# PMIC_V2.net
KiCad netlist of a schematic drawn in Altium Designer
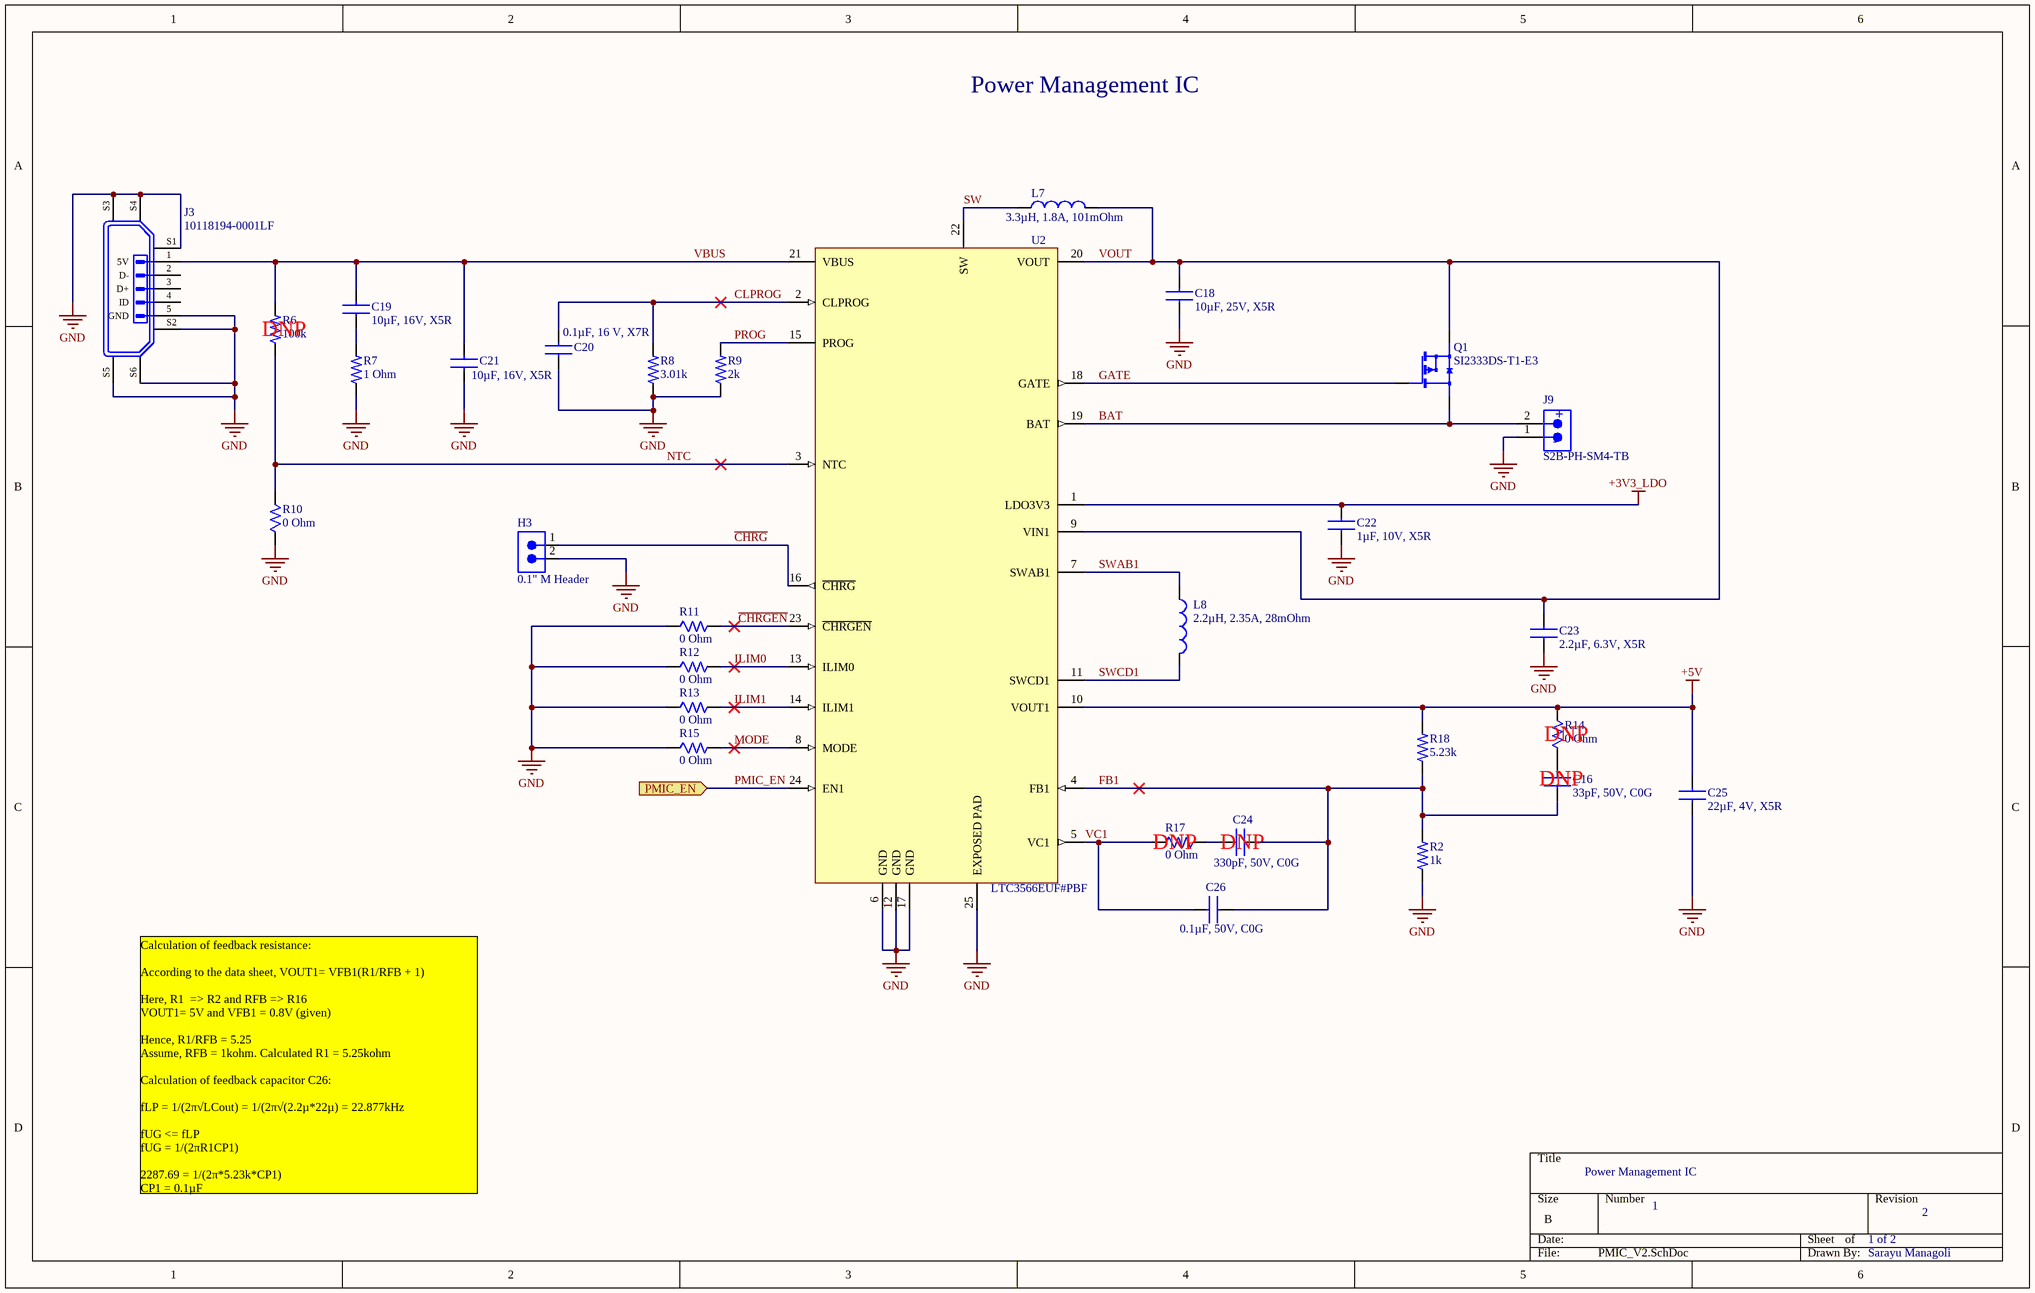
[diagram p0: PMIC_V2.SchDoc]

(export (version "E")
  (design (tool "Eeschema 10.0.6"))
  (components
    (comp (ref "C16")
      (value "33pF, 50V, C0G")
      (footprint "CAPC2012X09N_39P")
      (description "Cap Ceramic 33pF 50V C0G 5% SMD 0805 125C Paper T/R")
      (fields
        (field (name "MANUFACTURER") "KEMET")
        (field (name "MANUFACTURER PART NUMBER") "C0805C330J5GACTU")
      )
      (libsource (lib "PMIC_IR") (part "C0805C330J5GACTU"))
    )
    (comp (ref "C18")
      (value "10µF, 25V, X5R")
      (footprint "CAP_2012X14")
      (description "CAP CER 10UF 25V X5R 0805")
      (fields
        (field (name "MANUFACTURER") "Murata")
        (field (name "MANUFACTURER PART NUMBER") "GRM21BR61E106KA73K")
      )
      (libsource (lib "PMIC_IR") (part "GRM21BR61E106KA73K"))
    )
    (comp (ref "C19")
      (value "10µF, 16V, X5R")
      (footprint "CAP_2012X14")
      (description "CAP CER 10UF 16V X5R 0805")
      (fields
        (field (name "MANUFACTURER") "Murata")
        (field (name "MANUFACTURER PART NUMBER") "GRM21BR61C106KE15L")
      )
      (libsource (lib "PMIC_IR") (part "GRM21BR61C106KE15L"))
    )
    (comp (ref "C20")
      (value "0.1µF, 16 V, X7R")
      (footprint "CAPC2012X14N")
      (fields
        (field (name "MANUFACTURER") "Yageo")
        (field (name "MANUFACTURER PART NUMBER") "CC0805KRX7R7BB104")
        (field (name "TOLERANCE") "10%")
      )
      (libsource (lib "PMIC_IR") (part "CC0805KRX7R7BB104"))
    )
    (comp (ref "C21")
      (value "10µF, 16V, X5R")
      (footprint "CAP_2012X14")
      (description "CAP CER 10UF 16V X5R 0805")
      (fields
        (field (name "MANUFACTURER") "Murata")
        (field (name "MANUFACTURER PART NUMBER") "GRM21BR61C106KE15L")
      )
      (libsource (lib "PMIC_IR") (part "GRM21BR61C106KE15L"))
    )
    (comp (ref "C22")
      (value "1µF, 10V, X5R")
      (footprint "CAPC2012X14N_1")
      (description "CAP CER 1UF 10V X5R 0805")
      (fields
        (field (name "MANUFACTURER") "Kyocera AVX")
        (field (name "MANUFACTURER PART NUMBER") "0805ZD105KAT2A")
      )
      (libsource (lib "PMIC_IR") (part "0805ZD105KAT2A"))
    )
    (comp (ref "C23")
      (value "2.2µF, 6.3V, X5R")
      (footprint "CAPC2012X14N_2_2")
      (description "CAP CER 2.2UF 6.3V X5R 0805")
      (fields
        (field (name "MANUFACTURER") "Wurth Electronics")
        (field (name "MANUFACTURER PART NUMBER") "885012107001")
      )
      (libsource (lib "PMIC_IR") (part "885012107001"))
    )
    (comp (ref "C24")
      (value "330pF, 50V, C0G")
      (footprint "CAPC2012X09N_39P")
      (description "CAP CER 330PF 50V C0G/NP0 0805")
      (fields
        (field (name "MANUFACTURER") "KEMET")
        (field (name "MANUFACTURER PART NUMBER") "C0603C331K5GACTU")
      )
      (libsource (lib "PMIC_IR") (part "C0805C331K5GACTU"))
    )
    (comp (ref "C25")
      (value "22µF, 4V, X5R")
      (footprint "CAPC2012X14N_22")
      (description "CAP CER 22UF 4V X5R 0805")
      (fields
        (field (name "MANUFACTURER") "KEMET")
        (field (name "MANUFACTURER PART NUMBER") "C0805C226K7PAC7800")
      )
      (libsource (lib "PMIC_IR") (part "C0805C226K7PAC7800"))
    )
    (comp (ref "C26")
      (value "0.1µF, 50V, C0G")
      (footprint "CAPC2012X09N_39P")
      (description "0805 C 0.1µF Ceramic Multilayer Capacitor; 25 VDC; +125degC; C0G Dielec; +/-5%")
      (fields
        (field (name "MANUFACTURER") "KEMET")
        (field (name "MANUFACTURER PART NUMBER") "C0805C390J5GACTU")
      )
      (libsource (lib "PMIC_IR") (part "C0805C103J3GACTU"))
    )
    (comp (ref "H3")
      (value "0.1\" M Header")
      (footprint "77311-118-02LF_AMP")
      (description "Test point")
      (fields
        (field (name "MANUFACTURER") "Amphenol ICC / FCI")
        (field (name "MANUFACTURER PART NUMBER") "77311-118-02LF")
      )
      (libsource (lib "PMIC_IR") (part "77311-118-02LF"))
    )
    (comp (ref "J3")
      (value "micro-USB")
      (footprint "micro-USB")
      (description "10118194-0001LF micro-USB paste-in-pad")
      (fields
        (field (name "MANUFACTURER") "FCI")
        (field (name "MANUFACTURER PART NUMBER") "10118194-0001LF")
        (field (name ".CREATOR") "Kailey Shara")
        (field (name ".SCHCHECKED") "KS")
        (field (name ".PCBCHECKED") "KS")
      )
      (libsource (lib "PMIC_IR") (part "micro-USB"))
    )
    (comp (ref "J9")
      (value "S2B-PH-SM4-TB")
      (footprint "S2B-PH-SM4-TB")
      (description "JST PH Series, 2 Position, Side Entry, 2.00mm, Solder, Surface Mount, Natural")
      (fields
        (field (name "MANUFACTURER") "JST")
        (field (name "MANUFACTURER PART NUMBER") "S2B-PH-SM4-TB(LF)(SN)")
      )
      (libsource (lib "PMIC_IR") (part "S2B-PH-SM4-TB(LF)(SN)"))
    )
    (comp (ref "L7")
      (value "3.3µH, 1.8A, 101mOhm")
      (footprint "IND_2828x30")
      (fields
        (field (name "MANUFACTURER") "Wurth Electronics")
        (field (name "MANUFACTURER PART NUMBER") "744025003")
        (field (name "TOLERANCE") "20%")
      )
      (libsource (lib "PMIC_IR") (part "744025003"))
    )
    (comp (ref "L8")
      (value "2.2µH, 2.35A, 28mOhm")
      (footprint "INDP4848X30N_2_2")
      (fields
        (field (name "MANUFACTURER") "Wurth Electronics")
        (field (name "MANUFACTURER PART NUMBER") "7440430022")
        (field (name "TOLERANCE") "30%")
      )
      (libsource (lib "PMIC_IR") (part "7440430022"))
    )
    (comp (ref "Q1")
      (value "SI2333DS-T1-E3")
      (footprint "SOT95P237X112-3N")
      (description "Mosfet; Power; P-ch; Vdss -12V; Rds(on) 0.025 Ohm; Id -4.1A; TO-236 (SOT-23); Pd 0.75W")
      (fields (field (name "MANUFACTURER") "Vishay Siliconix"))
      (libsource (lib "PMIC_IR") (part "SI2333DS-T1-E3"))
    )
    (comp (ref "R2")
      (value "1k")
      (footprint "RESC1609X05N")
      (description "Res Thick Film 0603 1K Ohm 1% 1/10W ±100ppm/°C Molded SMD SMD T/R")
      (fields
        (field (name "MANUFACTURER") "Vishay")
        (field (name "MANUFACTURER PART NUMBER") "CHPHT0603K1001FGT")
      )
      (libsource (lib "PMIC_IR") (part "CRCW06031K00FKEAC"))
    )
    (comp (ref "R6")
      (value "100k")
      (footprint "RESC1607X60N")
      (description "RES SMD 100K OHM 1% 1/10W 0603")
      (fields
        (field (name "MANUFACTURER") "Yageo")
        (field (name "MANUFACTURER PART NUMBER") "RC0603FR-07100KL")
      )
      (libsource (lib "PMIC_IR") (part "RC0603FR-07100KL"))
    )
    (comp (ref "R7")
      (value "1 Ohm")
      (footprint "RESC1508X06N")
      (description "YAGEO         RC0603FR-07100RL            RES, THICK FILM, 100R, 1%, 0.1W, 0603, REEL")
      (fields
        (field (name "MANUFACTURER") "Yageo")
        (field (name "MANUFACTURER PART NUMBER") "RC0603FR-07100RL")
      )
      (libsource (lib "PMIC_IR") (part "RC0603FR-07100RL"))
    )
    (comp (ref "R8")
      (value "3.01k")
      (footprint "RESC1608X06N_3K01")
      (description "RES SMD 3.01KOHM 0.1% 1/16W 0603")
      (fields
        (field (name "MANUFACTURER") "Stackpole Electronics")
        (field (name "MANUFACTURER PART NUMBER") "RNCS0603BKE3K01")
      )
      (libsource (lib "PMIC_IR") (part "RNCS0603BKE3K01"))
    )
    (comp (ref "R9")
      (value "2k")
      (footprint "RESC1508X06N")
      (description "RES SMD 2K OHM 1% 1/16W 0603")
      (fields
        (field (name "MANUFACTURER") "TE Connectivity")
        (field (name "MANUFACTURER PART NUMBER") "9-1879336-1")
      )
      (libsource (lib "PMIC_IR") (part "9-1879336-1"))
    )
    (comp (ref "R10")
      (value "0 Ohm")
      (footprint "RES_0_0603")
      (description "Jumper, 0 ohm, 0603 [Metrisch 1608], Baureihe RC, 75 V, Dickschicht")
      (fields
        (field (name "MANUFACTURER") "Yageo")
        (field (name "MANUFACTURER PART NUMBER") "RC0603JR-070RL")
      )
      (libsource (lib "PMIC_IR") (part "RC0603JR-070RL"))
    )
    (comp (ref "R11")
      (value "0 Ohm")
      (footprint "RES_0_0603")
      (description "Jumper, 0 ohm, 0603 [Metrisch 1608], Baureihe RC, 75 V, Dickschicht")
      (fields
        (field (name "MANUFACTURER") "Yageo")
        (field (name "MANUFACTURER PART NUMBER") "RC0603JR-070RL")
      )
      (libsource (lib "PMIC_IR") (part "RC0603JR-070RL"))
    )
    (comp (ref "R12")
      (value "0 Ohm")
      (footprint "RES_0_0603")
      (description "Jumper, 0 ohm, 0603 [Metrisch 1608], Baureihe RC, 75 V, Dickschicht")
      (fields
        (field (name "MANUFACTURER") "Yageo")
        (field (name "MANUFACTURER PART NUMBER") "RC0603JR-070RL")
      )
      (libsource (lib "PMIC_IR") (part "RC0603JR-070RL"))
    )
    (comp (ref "R13")
      (value "0 Ohm")
      (footprint "RES_0_0603")
      (description "Jumper, 0 ohm, 0603 [Metrisch 1608], Baureihe RC, 75 V, Dickschicht")
      (fields
        (field (name "MANUFACTURER") "Yageo")
        (field (name "MANUFACTURER PART NUMBER") "RC0603JR-070RL")
      )
      (libsource (lib "PMIC_IR") (part "RC0603JR-070RL"))
    )
    (comp (ref "R14")
      (value "0 Ohm")
      (footprint "RES_0_0603")
      (description "Jumper, 0 ohm, 0603 [Metrisch 1608], Baureihe RC, 75 V, Dickschicht")
      (fields
        (field (name "MANUFACTURER") "Yageo")
        (field (name "MANUFACTURER PART NUMBER") "RC0603JR-070RL")
      )
      (libsource (lib "PMIC_IR") (part "RC0603JR-070RL"))
    )
    (comp (ref "R15")
      (value "0 Ohm")
      (footprint "RES_0_0603")
      (description "Jumper, 0 ohm, 0603 [Metrisch 1608], Baureihe RC, 75 V, Dickschicht")
      (fields
        (field (name "MANUFACTURER") "Yageo")
        (field (name "MANUFACTURER PART NUMBER") "RC0603JR-070RL")
      )
      (libsource (lib "PMIC_IR") (part "RC0603JR-070RL"))
    )
    (comp (ref "R17")
      (value "0 Ohm")
      (footprint "RES_0_0603")
      (description "Jumper, 0 ohm, 0603 [Metrisch 1608], Baureihe RC, 75 V, Dickschicht")
      (fields
        (field (name "MANUFACTURER") "Yageo")
        (field (name "MANUFACTURER PART NUMBER") "RC0603JR-070RL")
      )
      (libsource (lib "PMIC_IR") (part "RC0603JR-070RL"))
    )
    (comp (ref "R18")
      (value "5.23k")
      (footprint "RES_0603_C1508X06N")
      (description "RES SMD 5.23K OHM 1% 1/10W 0603")
      (fields
        (field (name "MANUFACTURER") "Stackpole Electronics")
        (field (name "MANUFACTURER PART NUMBER") "RMCF0603FT5K23")
      )
      (libsource (lib "PMIC_IR") (part "RMCF0603FT5K23"))
    )
    (comp (ref "U2")
      (value "LTC3566EUF#PBF")
      (footprint "QFN50P400X400X80_HS")
      (description "IC, BATTERY CHARGER, 1.07A, QFN-24")
      (fields (field (name "MANUFACTURER") "Analog Devices / Linear Technology"))
      (libsource (lib "PMIC_IR") (part "LTC3566EUF#PBF"))
    )
  )
  (nets
    (net (code "1") (name "+3V3_LDO") (class "Default")
      (node (ref "C22") (pin "1") (pinfunction "1_1") (pintype "passive"))
      (node (ref "U2") (pin "1") (pinfunction "LDO3V3_1") (pintype "power_in"))
    )
    (net (code "2") (name "+5V") (class "Default")
      (node (ref "C25") (pin "2") (pinfunction "2_2") (pintype "passive"))
      (node (ref "R14") (pin "2") (pinfunction "2_2") (pintype "passive"))
      (node (ref "R18") (pin "2") (pinfunction "2_2") (pintype "passive"))
      (node (ref "U2") (pin "10") (pinfunction "VOUT1_10") (pintype "power_in"))
    )
    (net (code "3") (name "/BAT") (class "Default")
      (node (ref "J9") (pin "2") (pinfunction "+_2") (pintype "passive"))
      (node (ref "Q1") (pin "2") (pinfunction "2_2") (pintype "passive"))
      (node (ref "U2") (pin "19") (pinfunction "BAT_19") (pintype "output"))
    )
    (net (code "4") (name "/CLPROG") (class "Default")
      (node (ref "C20") (pin "1") (pinfunction "1_1") (pintype "passive"))
      (node (ref "R8") (pin "2") (pinfunction "2_2") (pintype "passive"))
      (node (ref "U2") (pin "2") (pinfunction "CLPROG_2") (pintype "input"))
    )
    (net (code "5") (name "/FB1") (class "Default")
      (node (ref "C16") (pin "2") (pinfunction "2_2") (pintype "passive"))
      (node (ref "C24") (pin "1") (pinfunction "1_1") (pintype "passive"))
      (node (ref "C26") (pin "1") (pinfunction "1_1") (pintype "passive"))
      (node (ref "R18") (pin "1") (pinfunction "1_1") (pintype "passive"))
      (node (ref "R2") (pin "2") (pinfunction "2_2") (pintype "passive"))
      (node (ref "U2") (pin "4") (pinfunction "FB1_4") (pintype "input"))
    )
    (net (code "6") (name "/GATE") (class "Default")
      (node (ref "Q1") (pin "3") (pinfunction "3_3") (pintype "passive"))
      (node (ref "U2") (pin "18") (pinfunction "GATE_18") (pintype "output"))
    )
    (net (code "10") (name "/ILIM0") (class "Default")
      (node (ref "R12") (pin "2") (pinfunction "2_2") (pintype "passive"))
      (node (ref "U2") (pin "13") (pinfunction "ILIM0_13") (pintype "input"))
    )
    (net (code "11") (name "/ILIM1") (class "Default")
      (node (ref "R13") (pin "2") (pinfunction "2_2") (pintype "passive"))
      (node (ref "U2") (pin "14") (pinfunction "ILIM1_14") (pintype "input"))
    )
    (net (code "12") (name "/MODE") (class "Default")
      (node (ref "R15") (pin "2") (pinfunction "2_2") (pintype "passive"))
      (node (ref "U2") (pin "8") (pinfunction "MODE_8") (pintype "input"))
    )
    (net (code "13") (name "/NTC") (class "Default")
      (node (ref "R10") (pin "2") (pinfunction "2_2") (pintype "passive"))
      (node (ref "R6") (pin "1") (pinfunction "1_1") (pintype "passive"))
      (node (ref "U2") (pin "3") (pinfunction "NTC_3") (pintype "input"))
    )
    (net (code "14") (name "/PMIC_EN") (class "Default")
      (node (ref "U2") (pin "24") (pinfunction "EN1_24") (pintype "input"))
    )
    (net (code "15") (name "/PROG") (class "Default")
      (node (ref "R9") (pin "2") (pinfunction "2_2") (pintype "passive"))
      (node (ref "U2") (pin "15") (pinfunction "PROG_15") (pintype "power_in"))
    )
    (net (code "16") (name "/SW") (class "Default")
      (node (ref "L7") (pin "1") (pinfunction "1_1") (pintype "passive"))
      (node (ref "U2") (pin "22") (pinfunction "SW_22") (pintype "power_in"))
    )
    (net (code "17") (name "/SWAB1") (class "Default")
      (node (ref "L8") (pin "1") (pinfunction "1_1") (pintype "passive"))
      (node (ref "U2") (pin "7") (pinfunction "SWAB1_7") (pintype "power_in"))
    )
    (net (code "18") (name "/SWCD1") (class "Default")
      (node (ref "L8") (pin "2") (pinfunction "2_2") (pintype "passive"))
      (node (ref "U2") (pin "11") (pinfunction "SWCD1_11") (pintype "power_in"))
    )
    (net (code "19") (name "/VBUS") (class "Default")
      (node (ref "C19") (pin "1") (pinfunction "1_1") (pintype "passive"))
      (node (ref "C21") (pin "1") (pinfunction "1_1") (pintype "passive"))
      (node (ref "J3") (pin "1") (pinfunction "5V_1") (pintype "power_in"))
      (node (ref "R6") (pin "2") (pinfunction "2_2") (pintype "passive"))
      (node (ref "U2") (pin "21") (pinfunction "VBUS_21") (pintype "power_in"))
    )
    (net (code "20") (name "/VC1") (class "Default")
      (node (ref "C26") (pin "2") (pinfunction "2_2") (pintype "passive"))
      (node (ref "R17") (pin "1") (pinfunction "1_1") (pintype "passive"))
      (node (ref "U2") (pin "5") (pinfunction "VC1_5") (pintype "output"))
    )
    (net (code "21") (name "/VOUT") (class "Default")
      (node (ref "C18") (pin "1") (pinfunction "1_1") (pintype "passive"))
      (node (ref "C23") (pin "2") (pinfunction "2_2") (pintype "passive"))
      (node (ref "L7") (pin "2") (pinfunction "2_2") (pintype "passive"))
      (node (ref "Q1") (pin "1") (pinfunction "1_1") (pintype "passive"))
      (node (ref "U2") (pin "20") (pinfunction "VOUT_20") (pintype "power_in"))
      (node (ref "U2") (pin "9") (pinfunction "VIN1_9") (pintype "power_in"))
    )
    (net (code "22") (name "/~{CHRGEN}") (class "Default")
      (node (ref "R11") (pin "2") (pinfunction "2_2") (pintype "passive"))
      (node (ref "U2") (pin "23") (pinfunction "~{CHRGEN}_23") (pintype "input"))
    )
    (net (code "23") (name "/~{CHRG}") (class "Default")
      (node (ref "H3") (pin "1") (pinfunction "1_1") (pintype "passive"))
      (node (ref "U2") (pin "16") (pinfunction "~{CHRG}_16") (pintype "output"))
    )
    (net (code "24") (name "GND") (class "Default")
      (node (ref "C18") (pin "2") (pinfunction "2_2") (pintype "passive"))
      (node (ref "C20") (pin "2") (pinfunction "2_2") (pintype "passive"))
      (node (ref "C21") (pin "2") (pinfunction "2_2") (pintype "passive"))
      (node (ref "C22") (pin "2") (pinfunction "2_2") (pintype "passive"))
      (node (ref "C23") (pin "1") (pinfunction "1_1") (pintype "passive"))
      (node (ref "C25") (pin "1") (pinfunction "1_1") (pintype "passive"))
      (node (ref "H3") (pin "2") (pinfunction "1_2") (pintype "passive"))
      (node (ref "J3") (pin "5") (pinfunction "GND_5") (pintype "power_in"))
      (node (ref "J3") (pin "S1") (pinfunction "GND_S1") (pintype "power_in"))
      (node (ref "J3") (pin "S2") (pinfunction "GND_S2") (pintype "power_in"))
      (node (ref "J3") (pin "S3") (pinfunction "GND_S3") (pintype "power_in"))
      (node (ref "J3") (pin "S4") (pinfunction "GND_S4") (pintype "power_in"))
      (node (ref "J3") (pin "S5") (pinfunction "GND_S5") (pintype "power_in"))
      (node (ref "J3") (pin "S6") (pinfunction "GND_S6") (pintype "power_in"))
      (node (ref "J9") (pin "1") (pinfunction "-_1") (pintype "passive"))
      (node (ref "R10") (pin "1") (pinfunction "1_1") (pintype "passive"))
      (node (ref "R11") (pin "1") (pinfunction "1_1") (pintype "passive"))
      (node (ref "R12") (pin "1") (pinfunction "1_1") (pintype "passive"))
      (node (ref "R13") (pin "1") (pinfunction "1_1") (pintype "passive"))
      (node (ref "R15") (pin "1") (pinfunction "1_1") (pintype "passive"))
      (node (ref "R2") (pin "1") (pinfunction "1_1") (pintype "passive"))
      (node (ref "R7") (pin "1") (pinfunction "1_1") (pintype "passive"))
      (node (ref "R8") (pin "1") (pinfunction "1_1") (pintype "passive"))
      (node (ref "R9") (pin "1") (pinfunction "1_1") (pintype "passive"))
      (node (ref "U2") (pin "12") (pinfunction "GND_12") (pintype "power_in"))
      (node (ref "U2") (pin "17") (pinfunction "GND_17") (pintype "power_in"))
      (node (ref "U2") (pin "25") (pinfunction "EXPOSED_PAD_25") (pintype "power_in"))
      (node (ref "U2") (pin "6") (pinfunction "GND_6") (pintype "power_in"))
    )
    (net (code "25") (name "Net-(C16-Pad1)") (class "Default")
      (node (ref "C16") (pin "1") (pinfunction "1_1") (pintype "passive"))
      (node (ref "R14") (pin "1") (pinfunction "1_1") (pintype "passive"))
    )
    (net (code "26") (name "Net-(C19-Pad2)") (class "Default")
      (node (ref "C19") (pin "2") (pinfunction "2_2") (pintype "passive"))
      (node (ref "R7") (pin "2") (pinfunction "2_2") (pintype "passive"))
    )
    (net (code "27") (name "Net-(C24-Pad2)") (class "Default")
      (node (ref "C24") (pin "2") (pinfunction "2_2") (pintype "passive"))
      (node (ref "R17") (pin "2") (pinfunction "2_2") (pintype "passive"))
    )
    (net (code "28") (name "unconnected-(J3-D+-Pad3)") (class "Default")
      (node (ref "J3") (pin "3") (pinfunction "D+_3") (pintype "passive"))
    )
    (net (code "29") (name "unconnected-(J3-D--Pad2)") (class "Default")
      (node (ref "J3") (pin "2") (pinfunction "D-_2") (pintype "passive"))
    )
    (net (code "30") (name "unconnected-(J3-ID-Pad4)") (class "Default")
      (node (ref "J3") (pin "4") (pinfunction "ID_4") (pintype "passive"))
    )
  )
)
